# MCU025A_XDS110_Target_Interface.net
KiCad netlist of a schematic drawn in Altium Designer
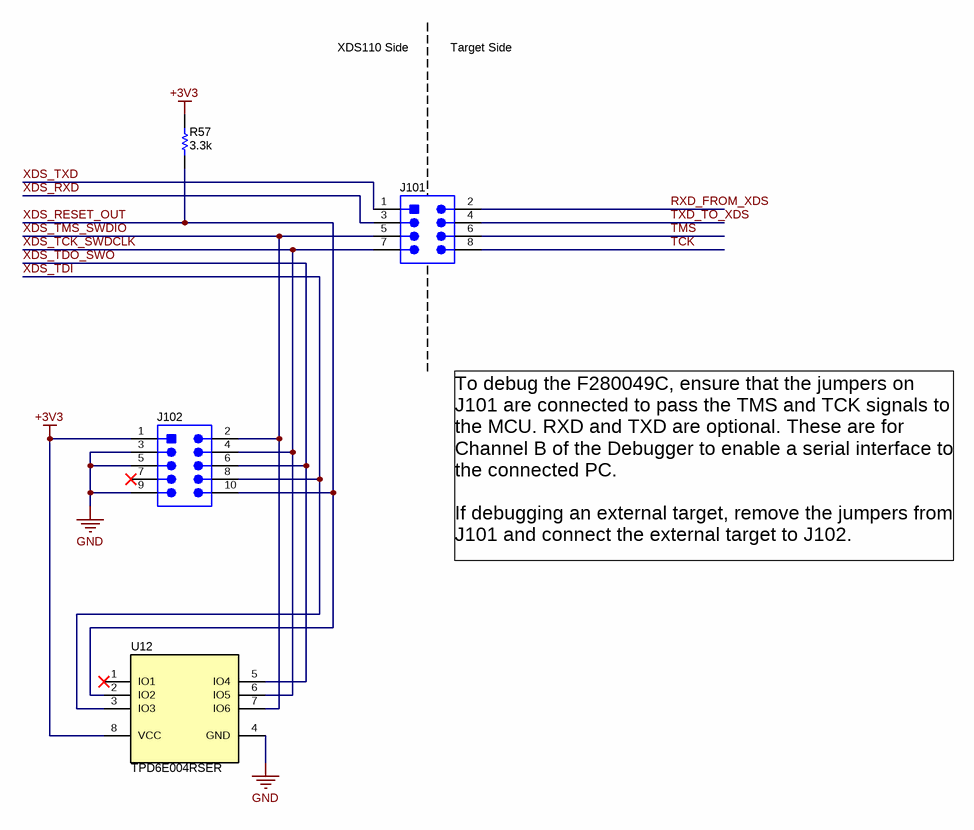
[diagram p0: MCU025A_XDS110_Target_Interface.SchDoc]

(export (version "E")
  (design (tool "Eeschema 10.0.6"))
  (components
    (comp (ref "J101")
      (value "TSW-104-07-G-D")
      (footprint "TSW-104-07-G-D")
      (description "Header, 100mil, 4x2, Gold, TH")
      (fields (field (name "MANUFACTURER") "Samtec") (field (name "PUBLISHER") "Texas Instruments"))
      (libsource (lib "Altium Vault - TI") (part "CMP-0075408-1"))
    )
    (comp (ref "J102")
      (value "FTSH-105-01-F-DV-K")
      (footprint "Samtec_FTSH-105-01-x-DV-K")
      (description "Header (Shrouded), 1.27mm, 5x2, Gold, SMT")
      (fields (field (name "MANUFACTURER") "Samtec") (field (name "PUBLISHER") "Texas Instruments"))
      (libsource (lib "Altium Vault - TI") (part "CMP-0075670-1"))
    )
    (comp (ref "R57")
      (value "CRCW04023K30JNED")
      (footprint "0402")
      (description "RES, 3.3 k, 5%, 0.063 W, AEC-Q200 Grade 0, 0402")
      (fields (field (name "VALUEDISPLAYED") "3.3k") (field (name "MANUFACTURER") "Vishay-Dale"))
      (libsource (lib "Altium Vault - TI") (part "Resistor"))
    )
    (comp (ref "U12")
      (value "TPD6E004RSER")
      (footprint "RSE0008A")
      (fields (field (name "MANUFACTURER") "Texas Instruments"))
      (libsource (lib "Altium Vault - TI") (part "TI-TPD6E004-UQFN_RSE-8"))
    )
  )
  (nets
    (net (code "1") (name "+3V3") (class "Default")
      (node (ref "J102") (pin "1") (pinfunction "1_1") (pintype "passive"))
      (node (ref "R57") (pin "2") (pinfunction "2_2") (pintype "passive"))
      (node (ref "U12") (pin "8") (pinfunction "VCC_8") (pintype "power_in"))
    )
    (net (code "2") (name "/RXD_FROM_XDS") (class "Default")
      (node (ref "J101") (pin "2") (pinfunction "2_2") (pintype "passive"))
    )
    (net (code "3") (name "/TCK") (class "Default")
      (node (ref "J101") (pin "8") (pinfunction "8_8") (pintype "passive"))
    )
    (net (code "4") (name "/TMS") (class "Default")
      (node (ref "J101") (pin "6") (pinfunction "6_6") (pintype "passive"))
    )
    (net (code "5") (name "/TXD_TO_XDS") (class "Default")
      (node (ref "J101") (pin "4") (pinfunction "4_4") (pintype "passive"))
    )
    (net (code "6") (name "/XDS_RESET_OUT") (class "Default")
      (node (ref "J102") (pin "10") (pinfunction "10_10") (pintype "passive"))
      (node (ref "R57") (pin "1") (pinfunction "1_1") (pintype "passive"))
      (node (ref "U12") (pin "2") (pinfunction "IO2_2") (pintype "passive"))
    )
    (net (code "7") (name "/XDS_RXD") (class "Default")
      (node (ref "J101") (pin "3") (pinfunction "3_3") (pintype "passive"))
    )
    (net (code "8") (name "/XDS_TCK_SWDCLK") (class "Default")
      (node (ref "J101") (pin "7") (pinfunction "7_7") (pintype "passive"))
      (node (ref "J102") (pin "4") (pinfunction "4_4") (pintype "passive"))
      (node (ref "U12") (pin "6") (pinfunction "IO5_6") (pintype "passive"))
    )
    (net (code "9") (name "/XDS_TDI") (class "Default")
      (node (ref "J102") (pin "8") (pinfunction "8_8") (pintype "passive"))
      (node (ref "U12") (pin "3") (pinfunction "IO3_3") (pintype "passive"))
    )
    (net (code "10") (name "/XDS_TDO_SWO") (class "Default")
      (node (ref "J102") (pin "6") (pinfunction "6_6") (pintype "passive"))
      (node (ref "U12") (pin "5") (pinfunction "IO4_5") (pintype "passive"))
    )
    (net (code "11") (name "/XDS_TMS_SWDIO") (class "Default")
      (node (ref "J101") (pin "5") (pinfunction "5_5") (pintype "passive"))
      (node (ref "J102") (pin "2") (pinfunction "2_2") (pintype "passive"))
      (node (ref "U12") (pin "7") (pinfunction "IO6_7") (pintype "passive"))
    )
    (net (code "12") (name "/XDS_TXD") (class "Default")
      (node (ref "J101") (pin "1") (pinfunction "1_1") (pintype "passive"))
    )
    (net (code "13") (name "GND") (class "Default")
      (node (ref "J102") (pin "3") (pinfunction "3_3") (pintype "passive"))
      (node (ref "J102") (pin "5") (pinfunction "5_5") (pintype "passive"))
      (node (ref "J102") (pin "9") (pinfunction "9_9") (pintype "passive"))
      (node (ref "U12") (pin "4") (pinfunction "GND_4") (pintype "power_in"))
    )
    (net (code "14") (name "unconnected-(J102-Pad7)") (class "Default")
      (node (ref "J102") (pin "7") (pinfunction "7_7") (pintype "passive+no_connect"))
    )
    (net (code "15") (name "unconnected-(U12-IO1-Pad1)") (class "Default")
      (node (ref "U12") (pin "1") (pinfunction "IO1_1") (pintype "passive+no_connect"))
    )
  )
)
